# mag_pos_adapter.net
KiCad netlist of a schematic drawn in Altium Designer
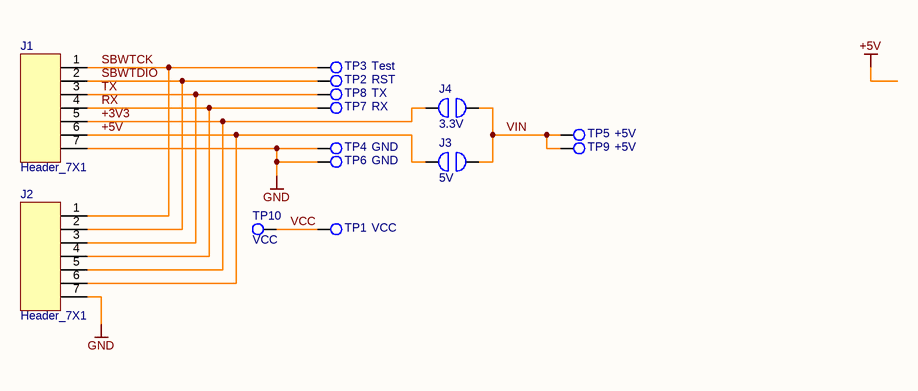
[diagram p0: mag_pos_adapter.SchDoc]

(export (version "E")
  (design (tool "Eeschema 10.0.6"))
  (components
    (comp (ref "J1")
      (value "Header_7X1")
      (footprint "mag_pos:HDRV7W64P254_1X7_1778X254X800P")
      (description "Header 7x1 pins")
      (libsource (lib "mag_pos") (part "Header_7X1"))
    )
    (comp (ref "J2")
      (value "Header_7X1")
      (footprint "mag_pos:HDRV7W64P254_1X7_1778X254X800P")
      (description "Header 7x1 pins")
      (libsource (lib "mag_pos") (part "Header_7X1"))
    )
    (comp (ref "J3")
      (value "5V")
      (footprint "AHO_Altium_Lib:Solder_Jumper_2pin_0.2mm")
      (libsource (lib "AHO_Altium_Lib") (part "SolderJumper_2"))
    )
    (comp (ref "J4")
      (value "3.3V")
      (footprint "AHO_Altium_Lib:Solder_Jumper_2pin_0.2mm")
      (libsource (lib "AHO_Altium_Lib") (part "SolderJumper_2"))
    )
    (comp (ref "TP1")
      (value "VCC")
      (footprint "mag_pos:TP_SPRING_PROBE_1.7MM_2.5MM")
      (description "Spring probe sleeve 1.7mm hole diameter, 2.5mm pad size, Harwin S25-022")
      (libsource (lib "mag_pos") (part "TP_SPRING_PROBE_1.7MM"))
    )
    (comp (ref "TP2")
      (value "RST")
      (footprint "mag_pos:TP_SPRING_PROBE_1.7MM_2.5MM")
      (description "Spring probe sleeve 1.7mm hole diameter, 2.5mm pad size, Harwin S25-022")
      (libsource (lib "mag_pos") (part "TP_SPRING_PROBE_1.7MM"))
    )
    (comp (ref "TP3")
      (value "Test")
      (footprint "mag_pos:TP_SPRING_PROBE_1.7MM_2.5MM")
      (description "Spring probe sleeve 1.7mm hole diameter, 2.5mm pad size, Harwin S25-022")
      (libsource (lib "mag_pos") (part "TP_SPRING_PROBE_1.7MM"))
    )
    (comp (ref "TP4")
      (value "GND")
      (footprint "mag_pos:TP_SPRING_PROBE_1.7MM_2.5MM")
      (description "Spring probe sleeve 1.7mm hole diameter, 2.5mm pad size, Harwin S25-022")
      (libsource (lib "mag_pos") (part "TP_SPRING_PROBE_1.7MM"))
    )
    (comp (ref "TP5")
      (value "+5V")
      (footprint "mag_pos:TP_SPRING_PROBE_1.7MM_2.5MM")
      (description "Spring probe sleeve 1.7mm hole diameter, 2.5mm pad size, Harwin S25-022")
      (libsource (lib "mag_pos") (part "TP_SPRING_PROBE_1.7MM"))
    )
    (comp (ref "TP6")
      (value "GND")
      (footprint "mag_pos:TP_SPRING_PROBE_1.7MM_2.5MM")
      (description "Spring probe sleeve 1.7mm hole diameter, 2.5mm pad size, Harwin S25-022")
      (libsource (lib "mag_pos") (part "TP_SPRING_PROBE_1.7MM"))
    )
    (comp (ref "TP7")
      (value "RX")
      (footprint "mag_pos:TP_SPRING_PROBE_1.7MM_2.5MM")
      (description "Spring probe sleeve 1.7mm hole diameter, 2.5mm pad size, Harwin S25-022")
      (libsource (lib "mag_pos") (part "TP_SPRING_PROBE_1.7MM"))
    )
    (comp (ref "TP8")
      (value "TX")
      (footprint "mag_pos:TP_SPRING_PROBE_1.7MM_2.5MM")
      (description "Spring probe sleeve 1.7mm hole diameter, 2.5mm pad size, Harwin S25-022")
      (libsource (lib "mag_pos") (part "TP_SPRING_PROBE_1.7MM"))
    )
    (comp (ref "TP9")
      (value "+5V")
      (footprint "mag_pos:TP_SPRING_PROBE_1.7MM_2.5MM")
      (description "Spring probe sleeve 1.7mm hole diameter, 2.5mm pad size, Harwin S25-022")
      (libsource (lib "mag_pos") (part "TP_SPRING_PROBE_1.7MM"))
    )
    (comp (ref "TP10")
      (value "VCC")
      (footprint "mag_pos:TP_SMD_1MM")
      (description "Testpoint SMD 1mm")
      (libsource (lib "mag_pos") (part "TP_SMD_1mm"))
    )
  )
  (nets
    (net (code "1") (name "+5V") (class "Default")
      (node (ref "J1") (pin "6") (pinfunction "6_6") (pintype "passive"))
      (node (ref "J2") (pin "6") (pinfunction "6_6") (pintype "passive"))
      (node (ref "J3") (pin "1") (pinfunction "1_1") (pintype "passive"))
    )
    (net (code "2") (name "/+3V3") (class "Default")
      (node (ref "J1") (pin "5") (pinfunction "5_5") (pintype "passive"))
      (node (ref "J2") (pin "5") (pinfunction "5_5") (pintype "passive"))
      (node (ref "J4") (pin "1") (pinfunction "1_1") (pintype "passive"))
    )
    (net (code "3") (name "/RX") (class "Default")
      (node (ref "J1") (pin "4") (pinfunction "4_4") (pintype "passive"))
      (node (ref "J2") (pin "4") (pinfunction "4_4") (pintype "passive"))
      (node (ref "TP7") (pin "1") (pinfunction "1_1") (pintype "passive"))
    )
    (net (code "4") (name "/SBWTCK") (class "Default")
      (node (ref "J1") (pin "1") (pinfunction "1_1") (pintype "passive"))
      (node (ref "J2") (pin "1") (pinfunction "1_1") (pintype "passive"))
      (node (ref "TP3") (pin "1") (pinfunction "1_1") (pintype "passive"))
    )
    (net (code "5") (name "/SBWTDIO") (class "Default")
      (node (ref "J1") (pin "2") (pinfunction "2_2") (pintype "passive"))
      (node (ref "J2") (pin "2") (pinfunction "2_2") (pintype "passive"))
      (node (ref "TP2") (pin "1") (pinfunction "1_1") (pintype "passive"))
    )
    (net (code "6") (name "/TX") (class "Default")
      (node (ref "J1") (pin "3") (pinfunction "3_3") (pintype "passive"))
      (node (ref "J2") (pin "3") (pinfunction "3_3") (pintype "passive"))
      (node (ref "TP8") (pin "1") (pinfunction "1_1") (pintype "passive"))
    )
    (net (code "7") (name "/VCC") (class "Default")
      (node (ref "TP1") (pin "1") (pinfunction "1_1") (pintype "passive"))
      (node (ref "TP10") (pin "1") (pinfunction "1_1") (pintype "passive"))
    )
    (net (code "8") (name "/VIN") (class "Default")
      (node (ref "J3") (pin "2") (pinfunction "2_2") (pintype "passive"))
      (node (ref "J4") (pin "2") (pinfunction "2_2") (pintype "passive"))
      (node (ref "TP5") (pin "1") (pinfunction "1_1") (pintype "passive"))
      (node (ref "TP9") (pin "1") (pinfunction "1_1") (pintype "passive"))
    )
    (net (code "9") (name "GND") (class "Default")
      (node (ref "J1") (pin "7") (pinfunction "7_7") (pintype "passive"))
      (node (ref "J2") (pin "7") (pinfunction "7_7") (pintype "passive"))
      (node (ref "TP4") (pin "1") (pinfunction "1_1") (pintype "passive"))
      (node (ref "TP6") (pin "1") (pinfunction "1_1") (pintype "passive"))
    )
  )
)
